# SIM_CARD.net
KiCad netlist of a schematic drawn in Altium Designer
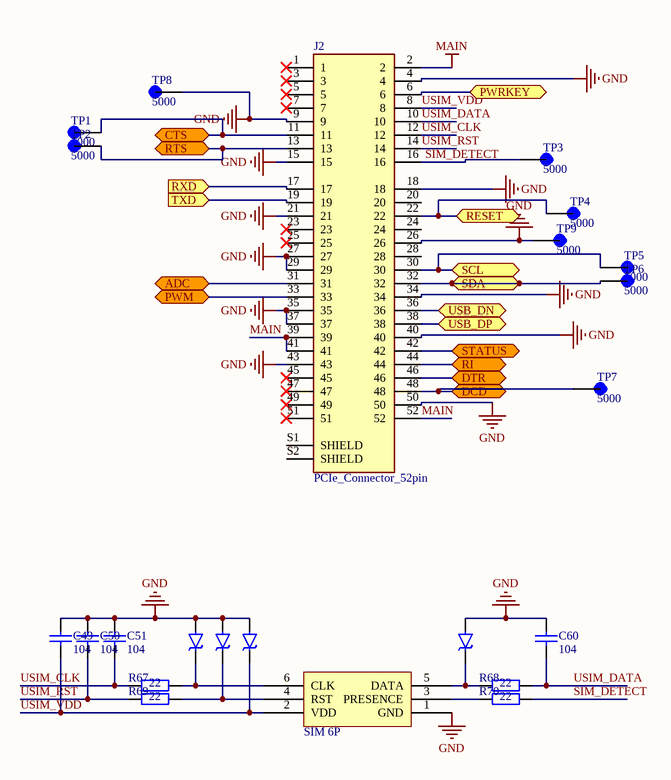
[diagram p0: SIM_CARD.SchDoc]

(export (version "E")
  (design (tool "Eeschema 10.0.6"))
  (components
    (comp (ref "C49")
      (value "104")
      (footprint "tu 0603")
      (description "Dán")
      (libsource (lib "Tu dien") (part "Tu 0603 104 50V 10%"))
    )
    (comp (ref "C50")
      (value "104")
      (footprint "tu 0603")
      (description "Dán")
      (libsource (lib "Tu dien") (part "Tu 0603 104 50V 10%"))
    )
    (comp (ref "C51")
      (value "104")
      (footprint "tu 0603")
      (description "Dán")
      (libsource (lib "Tu dien") (part "Tu 0603 104 50V 10%"))
    )
    (comp (ref "C60")
      (value "104")
      (footprint "tu 0603")
      (description "Dán")
      (libsource (lib "Tu dien") (part "Tu 0603 104 50V 10%"))
    )
    (comp (ref "J2")
      (value "PCIe_Connector_52pin")
      (footprint "Mini_PCIe_Connector:MOLEX_67910-0002")
      (description "52 Position Female Connector PCI Express Mini Card Gold 0.031 _0.80mm_ Black")
      (fields (field (name "MF") "Molex") (field (name "MP") "67910-0002"))
      (libsource (lib "Mini_PCIe_Connector") (part "PCIe_Connector_52pin"))
    )
    (comp (ref "R67")
      (value "22")
      (footprint "tro smd 0603")
      (description "Dán")
      (libsource (lib "Dien Tro") (part "Tro 0603 5% 3.3k"))
    )
    (comp (ref "R68")
      (value "22")
      (footprint "tro smd 0603")
      (description "Dán")
      (libsource (lib "Dien Tro") (part "Tro 0603 5% 3.3k"))
    )
    (comp (ref "R69")
      (value "22")
      (footprint "tro smd 0603")
      (description "Dán")
      (libsource (lib "Dien Tro") (part "Tro 0603 5% 3.3k"))
    )
    (comp (ref "R70")
      (value "22")
      (footprint "tro smd 0603")
      (description "Dán")
      (libsource (lib "Dien Tro") (part "Tro 0603 5% 3.3k"))
    )
    (comp (ref "SIM1") (value "SIM 6P") (footprint "sim6") (libsource (lib "Component") (part "Khay SIM 6P")))
    (comp (ref "TP1")
      (value "5000")
      (footprint "KEYSTONE_5000")
      (description "PC Test Point - Miniature")
      (fields (field (name "MF") "Keystone Electronics"))
      (libsource (lib "Test_Point") (part "5000"))
    )
    (comp (ref "TP2")
      (value "5000")
      (footprint "KEYSTONE_5000")
      (description "PC Test Point - Miniature")
      (fields (field (name "MF") "Keystone Electronics"))
      (libsource (lib "Test_Point") (part "5000"))
    )
    (comp (ref "TP3")
      (value "5000")
      (footprint "KEYSTONE_5000")
      (description "PC Test Point - Miniature")
      (fields (field (name "MF") "Keystone Electronics"))
      (libsource (lib "Test_Point") (part "5000"))
    )
    (comp (ref "TP4")
      (value "5000")
      (footprint "KEYSTONE_5000")
      (description "PC Test Point - Miniature")
      (fields (field (name "MF") "Keystone Electronics"))
      (libsource (lib "Test_Point") (part "5000"))
    )
    (comp (ref "TP5")
      (value "5000")
      (footprint "KEYSTONE_5000")
      (description "PC Test Point - Miniature")
      (fields (field (name "MF") "Keystone Electronics"))
      (libsource (lib "Test_Point") (part "5000"))
    )
    (comp (ref "TP6")
      (value "5000")
      (footprint "KEYSTONE_5000")
      (description "PC Test Point - Miniature")
      (fields (field (name "MF") "Keystone Electronics"))
      (libsource (lib "Test_Point") (part "5000"))
    )
    (comp (ref "TP7")
      (value "5000")
      (footprint "KEYSTONE_5000")
      (description "PC Test Point - Miniature")
      (fields (field (name "MF") "Keystone Electronics"))
      (libsource (lib "Test_Point") (part "5000"))
    )
    (comp (ref "TP8")
      (value "5000")
      (footprint "KEYSTONE_5000")
      (description "PC Test Point - Miniature")
      (fields (field (name "MF") "Keystone Electronics"))
      (libsource (lib "Test_Point") (part "5000"))
    )
    (comp (ref "TP9")
      (value "5000")
      (footprint "KEYSTONE_5000")
      (description "PC Test Point - Miniature")
      (fields (field (name "MF") "Keystone Electronics"))
      (libsource (lib "Test_Point") (part "5000"))
    )
    (comp (ref "TVS1")
      (value "TVS Diode")
      (footprint "SMA - DO-214AC")
      (libsource (lib "CMN") (part "TVS Uni Diode"))
    )
    (comp (ref "TVS2")
      (value "TVS Diode")
      (footprint "SMA - DO-214AC")
      (libsource (lib "CMN") (part "TVS Uni Diode"))
    )
    (comp (ref "TVS3")
      (value "TVS Diode")
      (footprint "SMA - DO-214AC")
      (libsource (lib "CMN") (part "TVS Uni Diode"))
    )
    (comp (ref "TVS4")
      (value "TVS Diode")
      (footprint "SMA - DO-214AC")
      (libsource (lib "CMN") (part "TVS Uni Diode"))
    )
  )
  (nets
    (net (code "1") (name "/ADC") (class "Default")
      (node (ref "J2") (pin "31") (pinfunction "31_31") (pintype "passive"))
    )
    (net (code "2") (name "/CTS") (class "Default")
      (node (ref "J2") (pin "11") (pinfunction "11_11") (pintype "passive"))
      (node (ref "TP1") (pin "TP") (pinfunction "TP_TP") (pintype "passive"))
    )
    (net (code "3") (name "/DCD") (class "Default")
      (node (ref "J2") (pin "48") (pinfunction "48_48") (pintype "passive"))
      (node (ref "TP7") (pin "TP") (pinfunction "TP_TP") (pintype "passive"))
    )
    (net (code "4") (name "/DTR") (class "Default")
      (node (ref "J2") (pin "46") (pinfunction "46_46") (pintype "passive"))
    )
    (net (code "5") (name "/PWM") (class "Default")
      (node (ref "J2") (pin "33") (pinfunction "33_33") (pintype "passive"))
    )
    (net (code "6") (name "/PWRKEY") (class "Default")
      (node (ref "J2") (pin "6") (pinfunction "6_6") (pintype "passive"))
    )
    (net (code "7") (name "/RESET") (class "Default")
      (node (ref "J2") (pin "22") (pinfunction "22_22") (pintype "passive"))
      (node (ref "TP4") (pin "TP") (pinfunction "TP_TP") (pintype "passive"))
    )
    (net (code "8") (name "/RI") (class "Default")
      (node (ref "J2") (pin "44") (pinfunction "44_44") (pintype "passive"))
    )
    (net (code "9") (name "/RTS") (class "Default")
      (node (ref "J2") (pin "13") (pinfunction "13_13") (pintype "passive"))
      (node (ref "TP2") (pin "TP") (pinfunction "TP_TP") (pintype "passive"))
    )
    (net (code "10") (name "/RXD") (class "Default")
      (node (ref "J2") (pin "17") (pinfunction "17_17") (pintype "passive"))
    )
    (net (code "11") (name "/SCL") (class "Default")
      (node (ref "J2") (pin "30") (pinfunction "30_30") (pintype "passive"))
      (node (ref "TP5") (pin "TP") (pinfunction "TP_TP") (pintype "passive"))
    )
    (net (code "12") (name "/SDA") (class "Default")
      (node (ref "J2") (pin "32") (pinfunction "32_32") (pintype "passive"))
      (node (ref "TP6") (pin "TP") (pinfunction "TP_TP") (pintype "passive"))
    )
    (net (code "13") (name "/SIM_DETECT") (class "Default")
      (node (ref "J2") (pin "16") (pinfunction "16_16") (pintype "passive"))
      (node (ref "R70") (pin "1") (pinfunction "1_1") (pintype "passive"))
      (node (ref "TP3") (pin "TP") (pinfunction "TP_TP") (pintype "passive"))
    )
    (net (code "14") (name "/STATUS") (class "Default")
      (node (ref "J2") (pin "42") (pinfunction "42_42") (pintype "passive"))
    )
    (net (code "15") (name "/TXD") (class "Default")
      (node (ref "J2") (pin "19") (pinfunction "19_19") (pintype "passive"))
    )
    (net (code "16") (name "/USB_DN") (class "Default")
      (node (ref "J2") (pin "36") (pinfunction "36_36") (pintype "passive"))
    )
    (net (code "17") (name "/USB_DP") (class "Default")
      (node (ref "J2") (pin "38") (pinfunction "38_38") (pintype "passive"))
    )
    (net (code "18") (name "/USIM_CLK") (class "Default")
      (node (ref "C51") (pin "2") (pinfunction "2_2") (pintype "passive"))
      (node (ref "J2") (pin "12") (pinfunction "12_12") (pintype "passive"))
      (node (ref "R67") (pin "2") (pinfunction "2_2") (pintype "passive"))
    )
    (net (code "19") (name "/USIM_DATA") (class "Default")
      (node (ref "C60") (pin "2") (pinfunction "2_2") (pintype "passive"))
      (node (ref "J2") (pin "10") (pinfunction "10_10") (pintype "passive"))
      (node (ref "R68") (pin "1") (pinfunction "1_1") (pintype "passive"))
    )
    (net (code "20") (name "/USIM_RST") (class "Default")
      (node (ref "C50") (pin "2") (pinfunction "2_2") (pintype "passive"))
      (node (ref "J2") (pin "14") (pinfunction "14_14") (pintype "passive"))
      (node (ref "R69") (pin "2") (pinfunction "2_2") (pintype "passive"))
    )
    (net (code "21") (name "/USIM_VDD") (class "Default")
      (node (ref "C49") (pin "2") (pinfunction "2_2") (pintype "passive"))
      (node (ref "J2") (pin "8") (pinfunction "8_8") (pintype "passive"))
      (node (ref "SIM1") (pin "2") (pinfunction "VDD_2") (pintype "passive"))
      (node (ref "TVS3") (pin "1") (pinfunction "1_1") (pintype "passive"))
    )
    (net (code "22") (name "GND") (class "Default")
      (node (ref "C49") (pin "1") (pinfunction "1_1") (pintype "passive"))
      (node (ref "C50") (pin "1") (pinfunction "1_1") (pintype "passive"))
      (node (ref "C51") (pin "1") (pinfunction "1_1") (pintype "passive"))
      (node (ref "C60") (pin "1") (pinfunction "1_1") (pintype "passive"))
      (node (ref "J2") (pin "15") (pinfunction "15_15") (pintype "passive"))
      (node (ref "J2") (pin "18") (pinfunction "18_18") (pintype "passive"))
      (node (ref "J2") (pin "21") (pinfunction "21_21") (pintype "passive"))
      (node (ref "J2") (pin "26") (pinfunction "26_26") (pintype "passive"))
      (node (ref "J2") (pin "27") (pinfunction "27_27") (pintype "passive"))
      (node (ref "J2") (pin "29") (pinfunction "29_29") (pintype "passive"))
      (node (ref "J2") (pin "34") (pinfunction "34_34") (pintype "passive"))
      (node (ref "J2") (pin "35") (pinfunction "35_35") (pintype "passive"))
      (node (ref "J2") (pin "37") (pinfunction "37_37") (pintype "passive"))
      (node (ref "J2") (pin "4") (pinfunction "4_4") (pintype "passive"))
      (node (ref "J2") (pin "40") (pinfunction "40_40") (pintype "passive"))
      (node (ref "J2") (pin "43") (pinfunction "43_43") (pintype "passive"))
      (node (ref "J2") (pin "50") (pinfunction "50_50") (pintype "passive"))
      (node (ref "J2") (pin "9") (pinfunction "9_9") (pintype "passive"))
      (node (ref "SIM1") (pin "1") (pinfunction "GND_1") (pintype "passive"))
      (node (ref "TP8") (pin "TP") (pinfunction "TP_TP") (pintype "passive"))
      (node (ref "TP9") (pin "TP") (pinfunction "TP_TP") (pintype "passive"))
      (node (ref "TVS1") (pin "2") (pinfunction "2_2") (pintype "passive"))
      (node (ref "TVS2") (pin "2") (pinfunction "2_2") (pintype "passive"))
      (node (ref "TVS3") (pin "2") (pinfunction "2_2") (pintype "passive"))
      (node (ref "TVS4") (pin "2") (pinfunction "2_2") (pintype "passive"))
    )
    (net (code "23") (name "MAIN") (class "Default")
      (node (ref "J2") (pin "2") (pinfunction "2_2") (pintype "passive"))
      (node (ref "J2") (pin "39") (pinfunction "39_39") (pintype "passive"))
      (node (ref "J2") (pin "41") (pinfunction "41_41") (pintype "passive"))
      (node (ref "J2") (pin "52") (pinfunction "52_52") (pintype "passive"))
    )
    (net (code "24") (name "Net-(SIM1-CLK)") (class "Default")
      (node (ref "R67") (pin "1") (pinfunction "1_1") (pintype "passive"))
      (node (ref "SIM1") (pin "6") (pinfunction "CLK_6") (pintype "passive"))
      (node (ref "TVS1") (pin "1") (pinfunction "1_1") (pintype "passive"))
    )
    (net (code "25") (name "Net-(SIM1-DATA)") (class "Default")
      (node (ref "R68") (pin "2") (pinfunction "2_2") (pintype "passive"))
      (node (ref "SIM1") (pin "5") (pinfunction "DATA_5") (pintype "passive"))
      (node (ref "TVS4") (pin "1") (pinfunction "1_1") (pintype "passive"))
    )
    (net (code "26") (name "Net-(SIM1-PRESENCE)") (class "Default")
      (node (ref "R70") (pin "2") (pinfunction "2_2") (pintype "passive"))
      (node (ref "SIM1") (pin "3") (pinfunction "PRESENCE_3") (pintype "passive"))
    )
    (net (code "27") (name "Net-(SIM1-RST)") (class "Default")
      (node (ref "R69") (pin "1") (pinfunction "1_1") (pintype "passive"))
      (node (ref "SIM1") (pin "4") (pinfunction "RST_4") (pintype "passive"))
      (node (ref "TVS2") (pin "1") (pinfunction "1_1") (pintype "passive"))
    )
    (net (code "28") (name "unconnected-(J2-Pad1)") (class "Default")
      (node (ref "J2") (pin "1") (pinfunction "1_1") (pintype "passive+no_connect"))
    )
    (net (code "29") (name "unconnected-(J2-Pad3)") (class "Default")
      (node (ref "J2") (pin "3") (pinfunction "3_3") (pintype "passive+no_connect"))
    )
    (net (code "30") (name "unconnected-(J2-Pad5)") (class "Default")
      (node (ref "J2") (pin "5") (pinfunction "5_5") (pintype "passive+no_connect"))
    )
    (net (code "31") (name "unconnected-(J2-Pad7)") (class "Default")
      (node (ref "J2") (pin "7") (pinfunction "7_7") (pintype "passive+no_connect"))
    )
    (net (code "32") (name "unconnected-(J2-Pad20)") (class "Default")
      (node (ref "J2") (pin "20") (pinfunction "20_20") (pintype "passive"))
    )
    (net (code "33") (name "unconnected-(J2-Pad23)") (class "Default")
      (node (ref "J2") (pin "23") (pinfunction "23_23") (pintype "passive+no_connect"))
    )
    (net (code "34") (name "unconnected-(J2-Pad24)") (class "Default")
      (node (ref "J2") (pin "24") (pinfunction "24_24") (pintype "passive"))
    )
    (net (code "35") (name "unconnected-(J2-Pad25)") (class "Default")
      (node (ref "J2") (pin "25") (pinfunction "25_25") (pintype "passive+no_connect"))
    )
    (net (code "36") (name "unconnected-(J2-Pad28)") (class "Default")
      (node (ref "J2") (pin "28") (pinfunction "28_28") (pintype "passive"))
    )
    (net (code "37") (name "unconnected-(J2-Pad45)") (class "Default")
      (node (ref "J2") (pin "45") (pinfunction "45_45") (pintype "passive+no_connect"))
    )
    (net (code "38") (name "unconnected-(J2-Pad47)") (class "Default")
      (node (ref "J2") (pin "47") (pinfunction "47_47") (pintype "passive+no_connect"))
    )
    (net (code "39") (name "unconnected-(J2-Pad49)") (class "Default")
      (node (ref "J2") (pin "49") (pinfunction "49_49") (pintype "passive+no_connect"))
    )
    (net (code "40") (name "unconnected-(J2-Pad51)") (class "Default")
      (node (ref "J2") (pin "51") (pinfunction "51_51") (pintype "passive+no_connect"))
    )
    (net (code "41") (name "unconnected-(J2-SHIELD-PadS1)") (class "Default")
      (node (ref "J2") (pin "S1") (pinfunction "SHIELD_S1") (pintype "passive"))
    )
    (net (code "42") (name "unconnected-(J2-SHIELD-PadS2)") (class "Default")
      (node (ref "J2") (pin "S2") (pinfunction "SHIELD_S2") (pintype "passive"))
    )
  )
)
